# encoder_avr.net
KiCad netlist of a schematic drawn in EAGLE
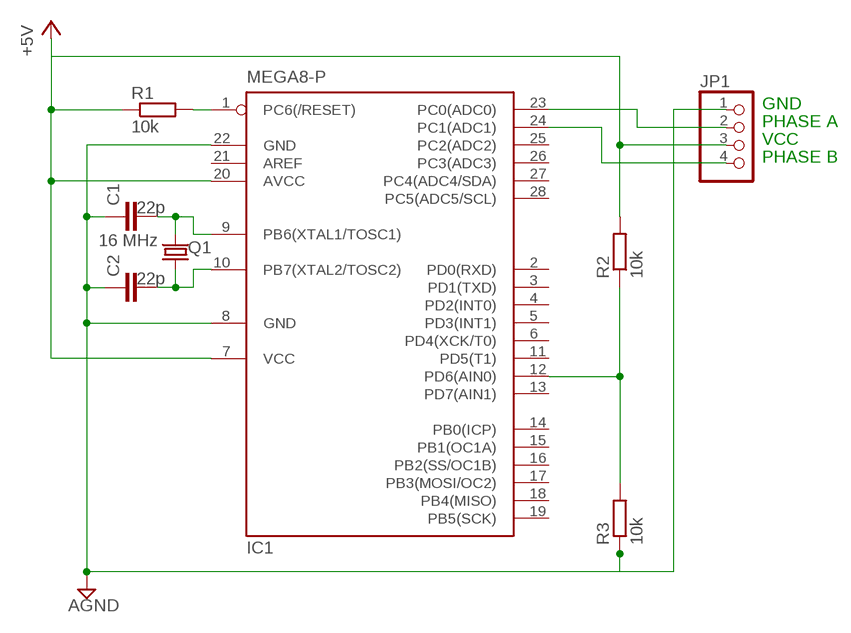
[diagram p0: schematic, sheet 1]

(export (version "E")
  (design (tool "Eeschema 10.0.6"))
  (components
    (comp (ref "C1")
      (value "22p")
      (footprint "eagle-import:C050-024X044")
      (libsource (lib "eagle-import") (part "C-EU050-024X044"))
    )
    (comp (ref "C2")
      (value "22p")
      (footprint "eagle-import:C050-024X044")
      (libsource (lib "eagle-import") (part "C-EU050-024X044"))
    )
    (comp (ref "IC1")
      (value "MEGA8-P")
      (footprint "eagle-import:DIL28-3")
      (libsource (lib "eagle-import") (part "MEGA8-P"))
    )
    (comp (ref "JP1")
      (value "PINHD-1X4")
      (footprint "eagle-import:1X04")
      (libsource (lib "eagle-import") (part "PINHD-1X4"))
    )
    (comp (ref "Q1")
      (value "16 MHz")
      (footprint "eagle-import:HC49_S")
      (libsource (lib "eagle-import") (part "CRYSTALHC49S"))
    )
    (comp (ref "R1")
      (value "10k")
      (footprint "eagle-import:0207_10")
      (libsource (lib "eagle-import") (part "R-EU_0207/10"))
    )
    (comp (ref "R2")
      (value "10k")
      (footprint "eagle-import:0207_10")
      (libsource (lib "eagle-import") (part "R-EU_0207/10"))
    )
    (comp (ref "R3")
      (value "10k")
      (footprint "eagle-import:0207_10")
      (libsource (lib "eagle-import") (part "R-EU_0207/10"))
    )
  )
  (nets
    (net (code "1") (name "+5V") (class "Default")
      (node (ref "IC1") (pin "20") (pinfunction "AVCC_20") (pintype "power_in"))
      (node (ref "IC1") (pin "7") (pinfunction "VCC_7") (pintype "power_in"))
      (node (ref "JP1") (pin "3") (pinfunction "3_3") (pintype "passive"))
      (node (ref "R1") (pin "1") (pinfunction "1_1") (pintype "passive"))
      (node (ref "R2") (pin "2") (pinfunction "2_2") (pintype "passive"))
    )
    (net (code "2") (name "AGND") (class "Default")
      (node (ref "C1") (pin "1") (pinfunction "1_1") (pintype "passive"))
      (node (ref "C2") (pin "1") (pinfunction "1_1") (pintype "passive"))
      (node (ref "IC1") (pin "22") (pinfunction "GND_22") (pintype "power_in"))
      (node (ref "IC1") (pin "8") (pinfunction "GND_8") (pintype "power_in"))
      (node (ref "JP1") (pin "1") (pinfunction "1_1") (pintype "passive"))
      (node (ref "R3") (pin "1") (pinfunction "1_1") (pintype "passive"))
    )
    (net (code "3") (name "Net-(IC1-PB6(XTAL1{slash}TOSC1))") (class "Default")
      (node (ref "C1") (pin "2") (pinfunction "2_2") (pintype "passive"))
      (node (ref "IC1") (pin "9") (pinfunction "PB6(XTAL1/TOSC1)_9") (pintype "bidirectional"))
      (node (ref "Q1") (pin "2") (pinfunction "2_2") (pintype "passive"))
    )
    (net (code "4") (name "Net-(IC1-PB7(XTAL2{slash}TOSC2))") (class "Default")
      (node (ref "C2") (pin "2") (pinfunction "2_2") (pintype "passive"))
      (node (ref "IC1") (pin "10") (pinfunction "PB7(XTAL2/TOSC2)_10") (pintype "bidirectional"))
      (node (ref "Q1") (pin "1") (pinfunction "1_1") (pintype "passive"))
    )
    (net (code "5") (name "Net-(IC1-PC0(ADC0))") (class "Default")
      (node (ref "IC1") (pin "23") (pinfunction "PC0(ADC0)_23") (pintype "bidirectional"))
      (node (ref "JP1") (pin "2") (pinfunction "2_2") (pintype "passive"))
    )
    (net (code "6") (name "Net-(IC1-PC1(ADC1))") (class "Default")
      (node (ref "IC1") (pin "24") (pinfunction "PC1(ADC1)_24") (pintype "bidirectional"))
      (node (ref "JP1") (pin "4") (pinfunction "4_4") (pintype "passive"))
    )
    (net (code "7") (name "Net-(IC1-PC6({slash}RESET))") (class "Default")
      (node (ref "IC1") (pin "1") (pinfunction "PC6(/RESET)_1") (pintype "bidirectional"))
      (node (ref "R1") (pin "2") (pinfunction "2_2") (pintype "passive"))
    )
    (net (code "8") (name "Net-(IC1-PD6(AIN0))") (class "Default")
      (node (ref "IC1") (pin "12") (pinfunction "PD6(AIN0)_12") (pintype "bidirectional"))
      (node (ref "R2") (pin "1") (pinfunction "1_1") (pintype "passive"))
      (node (ref "R3") (pin "2") (pinfunction "2_2") (pintype "passive"))
    )
    (net (code "9") (name "unconnected-(IC1-AREF-Pad21)") (class "Default")
      (node (ref "IC1") (pin "21") (pinfunction "AREF_21") (pintype "passive"))
    )
    (net (code "10") (name "unconnected-(IC1-PB0(ICP)-Pad14)") (class "Default")
      (node (ref "IC1") (pin "14") (pinfunction "PB0(ICP)_14") (pintype "bidirectional"))
    )
    (net (code "11") (name "unconnected-(IC1-PB1(OC1A)-Pad15)") (class "Default")
      (node (ref "IC1") (pin "15") (pinfunction "PB1(OC1A)_15") (pintype "bidirectional"))
    )
    (net (code "12") (name "unconnected-(IC1-PB2(SS{slash}OC1B)-Pad16)") (class "Default")
      (node (ref "IC1") (pin "16") (pinfunction "PB2(SS/OC1B)_16") (pintype "bidirectional"))
    )
    (net (code "13") (name "unconnected-(IC1-PB3(MOSI{slash}OC2)-Pad17)") (class "Default")
      (node (ref "IC1") (pin "17") (pinfunction "PB3(MOSI/OC2)_17") (pintype "bidirectional"))
    )
    (net (code "14") (name "unconnected-(IC1-PB4(MISO)-Pad18)") (class "Default")
      (node (ref "IC1") (pin "18") (pinfunction "PB4(MISO)_18") (pintype "bidirectional"))
    )
    (net (code "15") (name "unconnected-(IC1-PB5(SCK)-Pad19)") (class "Default")
      (node (ref "IC1") (pin "19") (pinfunction "PB5(SCK)_19") (pintype "bidirectional"))
    )
    (net (code "16") (name "unconnected-(IC1-PC2(ADC2)-Pad25)") (class "Default")
      (node (ref "IC1") (pin "25") (pinfunction "PC2(ADC2)_25") (pintype "bidirectional"))
    )
    (net (code "17") (name "unconnected-(IC1-PC3(ADC3)-Pad26)") (class "Default")
      (node (ref "IC1") (pin "26") (pinfunction "PC3(ADC3)_26") (pintype "bidirectional"))
    )
    (net (code "18") (name "unconnected-(IC1-PC4(ADC4{slash}SDA)-Pad27)") (class "Default")
      (node (ref "IC1") (pin "27") (pinfunction "PC4(ADC4/SDA)_27") (pintype "bidirectional"))
    )
    (net (code "19") (name "unconnected-(IC1-PC5(ADC5{slash}SCL)-Pad28)") (class "Default")
      (node (ref "IC1") (pin "28") (pinfunction "PC5(ADC5/SCL)_28") (pintype "bidirectional"))
    )
    (net (code "20") (name "unconnected-(IC1-PD0(RXD)-Pad2)") (class "Default")
      (node (ref "IC1") (pin "2") (pinfunction "PD0(RXD)_2") (pintype "bidirectional"))
    )
    (net (code "21") (name "unconnected-(IC1-PD1(TXD)-Pad3)") (class "Default")
      (node (ref "IC1") (pin "3") (pinfunction "PD1(TXD)_3") (pintype "bidirectional"))
    )
    (net (code "22") (name "unconnected-(IC1-PD2(INT0)-Pad4)") (class "Default")
      (node (ref "IC1") (pin "4") (pinfunction "PD2(INT0)_4") (pintype "bidirectional"))
    )
    (net (code "23") (name "unconnected-(IC1-PD3(INT1)-Pad5)") (class "Default")
      (node (ref "IC1") (pin "5") (pinfunction "PD3(INT1)_5") (pintype "bidirectional"))
    )
    (net (code "24") (name "unconnected-(IC1-PD4(XCK{slash}T0)-Pad6)") (class "Default")
      (node (ref "IC1") (pin "6") (pinfunction "PD4(XCK/T0)_6") (pintype "bidirectional"))
    )
    (net (code "25") (name "unconnected-(IC1-PD5(T1)-Pad11)") (class "Default")
      (node (ref "IC1") (pin "11") (pinfunction "PD5(T1)_11") (pintype "bidirectional"))
    )
    (net (code "26") (name "unconnected-(IC1-PD7(AIN1)-Pad13)") (class "Default")
      (node (ref "IC1") (pin "13") (pinfunction "PD7(AIN1)_13") (pintype "bidirectional"))
    )
  )
)
